# Grove_-_Capacitive_Moisture_Sensor_Corro.net
KiCad netlist of a schematic drawn in EAGLE
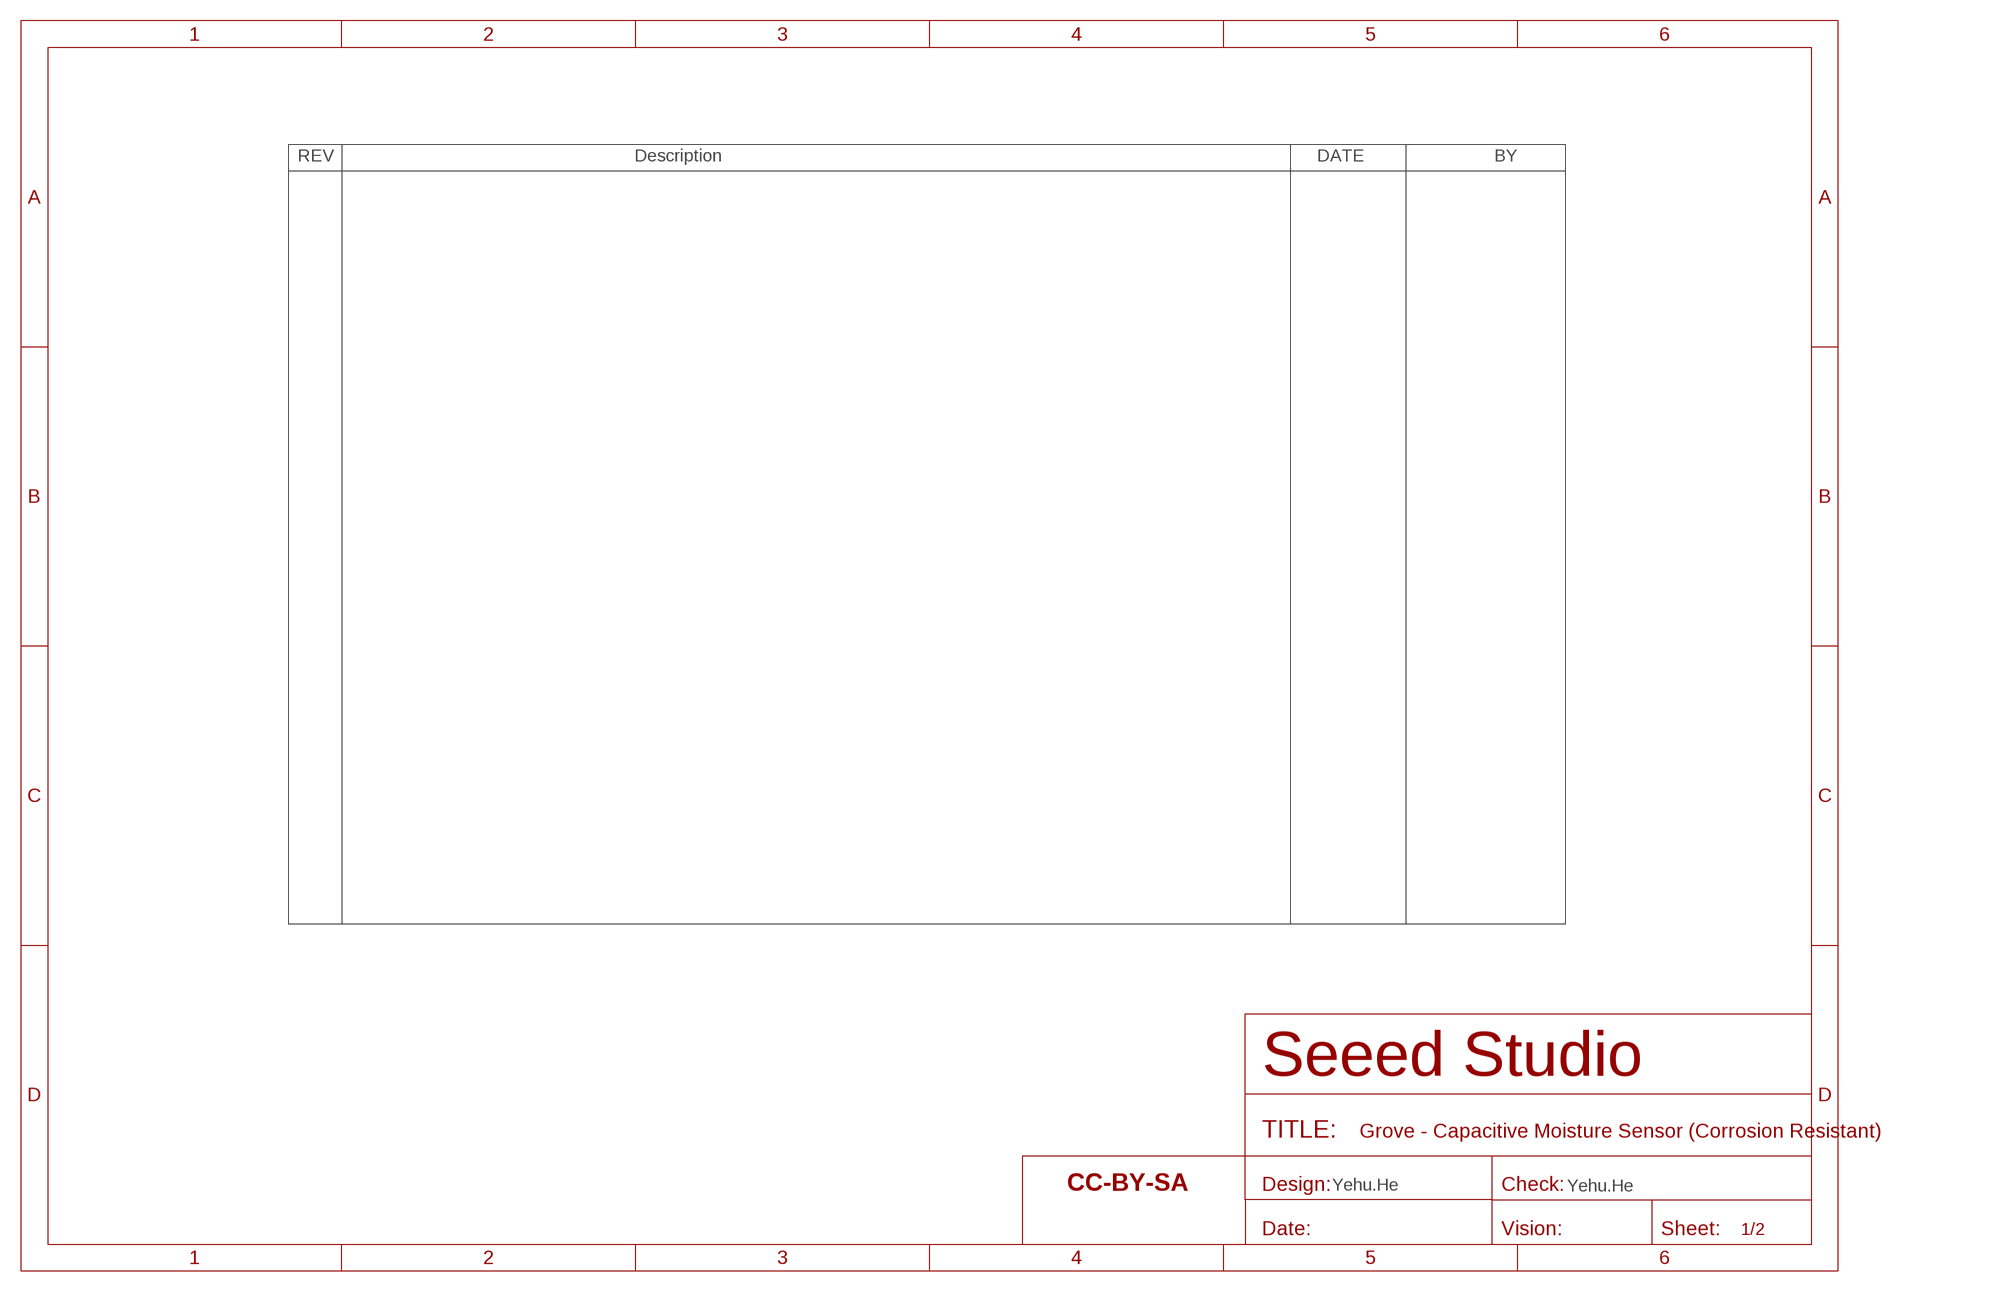
[diagram p0: schematic, sheet 1]
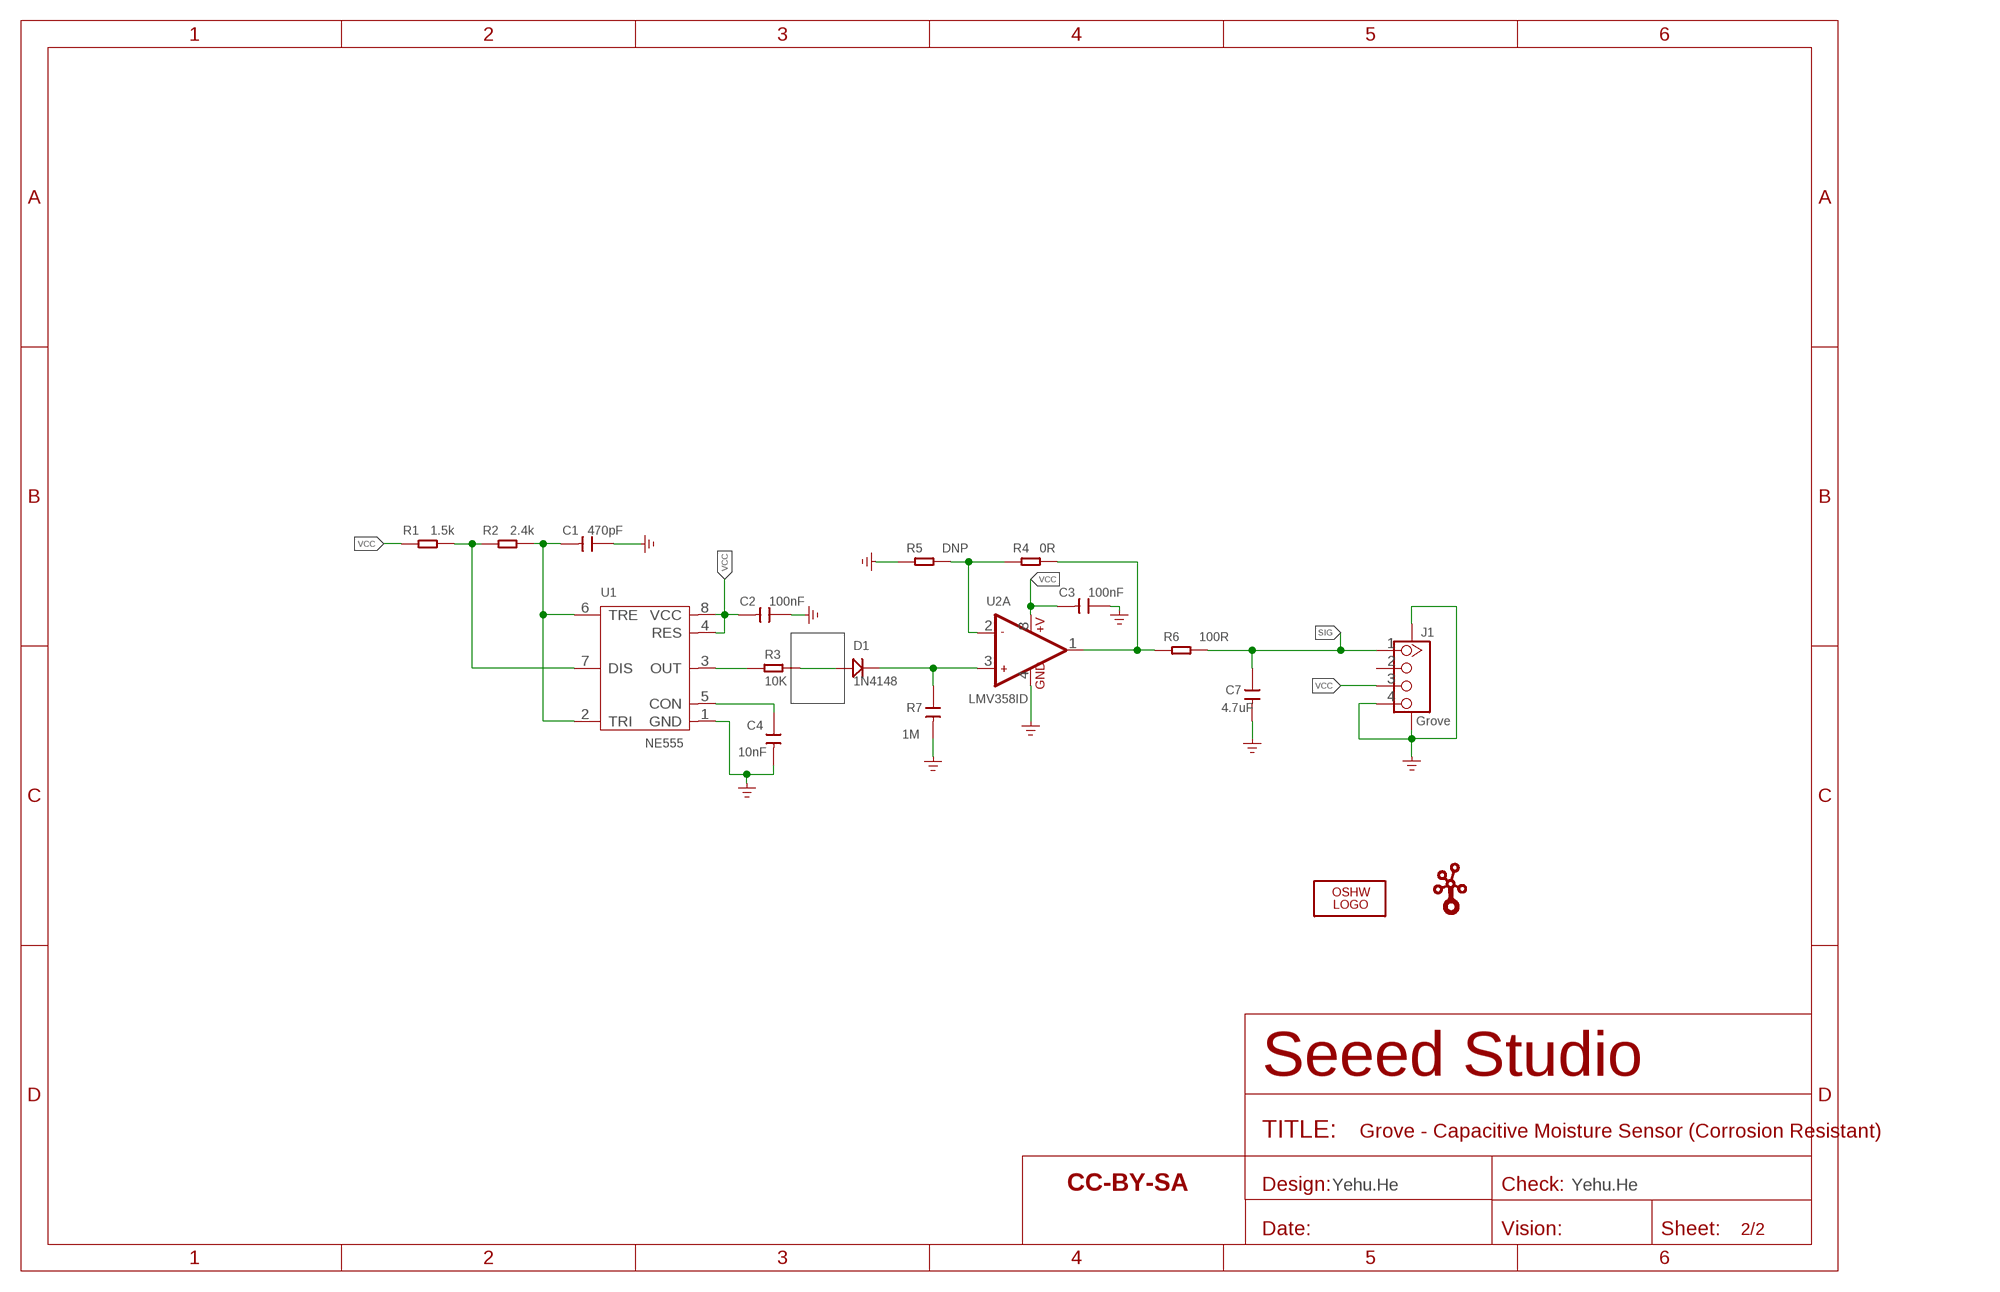
[diagram p1: schematic, sheet 2]

(export (version "E")
  (design (tool "Eeschema 10.0.6"))
  (components
    (comp (ref "C1")
      (value "470pF")
      (footprint "eagle-import:C0603")
      (libsource (lib "eagle-import") (part "CAP-0603"))
    )
    (comp (ref "C2")
      (value "100nF")
      (footprint "eagle-import:C0603")
      (libsource (lib "eagle-import") (part "CAP-0603"))
    )
    (comp (ref "C3")
      (value "100nF")
      (footprint "eagle-import:C0603")
      (libsource (lib "eagle-import") (part "CAP-0603"))
    )
    (comp (ref "C4")
      (value "10nF")
      (footprint "eagle-import:C0603")
      (libsource (lib "eagle-import") (part "CAP-0603"))
    )
    (comp (ref "C7")
      (value "4.7uF")
      (footprint "eagle-import:C0603")
      (libsource (lib "eagle-import") (part "CAP-0603"))
    )
    (comp (ref "D1")
      (value "1N4148")
      (footprint "eagle-import:LL-34")
      (libsource (lib "eagle-import") (part "DIODE'1N4148-SMD'"))
    )
    (comp (ref "FR2")
      (value "SEEEDSTUDIO-OPEN-SCH-FRAME")
      (footprint "eagle-import:SEEEDSTUDIO-PCB-FRAME")
      (libsource (lib "eagle-import") (part "SEEEDSTUDIO-OPEN-SCH-FRAME"))
    )
    (comp (ref "J1")
      (value "Grove")
      (footprint "eagle-import:HW4-SMD-2.0-90D")
      (libsource (lib "eagle-import") (part "GROVE-CONNECTOR-SMD'90D'"))
    )
    (comp (ref "LOGO1")
      (value "LOGO-OSHW-FILLX0200-NT")
      (footprint "eagle-import:OSHW_FILLX200_NOTEXT")
      (fields (field (name "PARTNO") "DNP"))
      (libsource (lib "eagle-import") (part "LOGO-OSHW-FILLX0200-NT"))
    )
    (comp (ref "R1")
      (value "1.5k")
      (footprint "eagle-import:R0603")
      (libsource (lib "eagle-import") (part "RES-0603"))
    )
    (comp (ref "R2")
      (value "2.4k")
      (footprint "eagle-import:R0603")
      (libsource (lib "eagle-import") (part "RES-0603"))
    )
    (comp (ref "R3")
      (value "10K")
      (footprint "eagle-import:R0603")
      (libsource (lib "eagle-import") (part "RES-0603"))
    )
    (comp (ref "R4")
      (value "0R")
      (footprint "eagle-import:R0603")
      (libsource (lib "eagle-import") (part "RES-0603"))
    )
    (comp (ref "R5")
      (value "DNP")
      (footprint "eagle-import:R0603")
      (libsource (lib "eagle-import") (part "RES-0603"))
    )
    (comp (ref "R6")
      (value "100R")
      (footprint "eagle-import:R0603")
      (libsource (lib "eagle-import") (part "RES-0603"))
    )
    (comp (ref "R7")
      (value "1M")
      (footprint "eagle-import:C0603")
      (libsource (lib "eagle-import") (part "CAP-0603"))
    )
    (comp (ref "U$7")
      (value "LOGO-GROVE")
      (footprint "eagle-import:GROVE-SILK-BIG")
      (fields (field (name "PARTNO") "DNP"))
      (libsource (lib "eagle-import") (part "LOGO-GROVE"))
    )
    (comp (ref "U1")
      (value "NE555")
      (footprint "eagle-import:SOIC8-1.27-5X4MM")
      (libsource (lib "eagle-import") (part "CLOCK/TIMING-NE555'DR'"))
    )
    (comp (ref "U2")
      (value "LMV358ID")
      (footprint "eagle-import:SOIC8-1.27-5X4MM")
      (libsource (lib "eagle-import") (part "AMPLIFIER-LMV358'D'"))
    )
    (comp (ref "FR1")
      (value "SEEEDSTUDIO-OPEN-SCH-FRAME")
      (footprint "eagle-import:SEEEDSTUDIO-PCB-FRAME")
      (libsource (lib "eagle-import") (part "SEEEDSTUDIO-OPEN-SCH-FRAME"))
    )
  )
  (nets
    (net (code "1") (name "GND") (class "Default")
      (node (ref "C1") (pin "1") (pinfunction "1_1") (pintype "passive"))
      (node (ref "C2") (pin "1") (pinfunction "1_1") (pintype "passive"))
      (node (ref "C3") (pin "1") (pinfunction "1_1") (pintype "passive"))
      (node (ref "C4") (pin "2") (pinfunction "2_2") (pintype "passive"))
      (node (ref "C7") (pin "2") (pinfunction "2_2") (pintype "passive"))
      (node (ref "J1") (pin "4") (pinfunction "4_4") (pintype "bidirectional"))
      (node (ref "J1") (pin "SS1") (pinfunction "SS1_SS1") (pintype "bidirectional"))
      (node (ref "J1") (pin "SS2") (pinfunction "SS2_SS2") (pintype "bidirectional"))
      (node (ref "R5") (pin "1") (pinfunction "1_1") (pintype "passive"))
      (node (ref "R7") (pin "2") (pinfunction "2_2") (pintype "passive"))
      (node (ref "U1") (pin "1") (pinfunction "GND_1") (pintype "bidirectional"))
      (node (ref "U2") (pin "4") (pinfunction "GND_4") (pintype "power_in"))
    )
    (net (code "2") (name "Net-(D1-+)") (class "Default")
      (node (ref "D1") (pin "A") (pinfunction "+_A") (pintype "passive"))
      (node (ref "R3") (pin "2") (pinfunction "2_2") (pintype "passive"))
    )
    (net (code "3") (name "Net-(D1--)") (class "Default")
      (node (ref "D1") (pin "C") (pinfunction "-_C") (pintype "passive"))
      (node (ref "R7") (pin "1") (pinfunction "1_1") (pintype "passive"))
      (node (ref "U2") (pin "3") (pinfunction "+IN1_3") (pintype "input"))
    )
    (net (code "4") (name "Net-(U1-CON)") (class "Default")
      (node (ref "C4") (pin "1") (pinfunction "1_1") (pintype "passive"))
      (node (ref "U1") (pin "5") (pinfunction "CON_5") (pintype "bidirectional"))
    )
    (net (code "5") (name "Net-(U1-DIS)") (class "Default")
      (node (ref "R1") (pin "1") (pinfunction "1_1") (pintype "passive"))
      (node (ref "R2") (pin "2") (pinfunction "2_2") (pintype "passive"))
      (node (ref "U1") (pin "7") (pinfunction "DIS_7") (pintype "bidirectional"))
    )
    (net (code "6") (name "Net-(U1-OUT)") (class "Default")
      (node (ref "R3") (pin "1") (pinfunction "1_1") (pintype "passive"))
      (node (ref "U1") (pin "3") (pinfunction "OUT_3") (pintype "bidirectional"))
    )
    (net (code "7") (name "Net-(U1-TRE)") (class "Default")
      (node (ref "C1") (pin "2") (pinfunction "2_2") (pintype "passive"))
      (node (ref "R2") (pin "1") (pinfunction "1_1") (pintype "passive"))
      (node (ref "U1") (pin "2") (pinfunction "TRI_2") (pintype "bidirectional"))
      (node (ref "U1") (pin "6") (pinfunction "TRE_6") (pintype "bidirectional"))
    )
    (net (code "8") (name "Net-(U2A--IN1)") (class "Default")
      (node (ref "R4") (pin "1") (pinfunction "1_1") (pintype "passive"))
      (node (ref "R5") (pin "2") (pinfunction "2_2") (pintype "passive"))
      (node (ref "U2") (pin "2") (pinfunction "-IN1_2") (pintype "input"))
    )
    (net (code "9") (name "Net-(U2A-OUT1)") (class "Default")
      (node (ref "R4") (pin "2") (pinfunction "2_2") (pintype "passive"))
      (node (ref "R6") (pin "1") (pinfunction "1_1") (pintype "passive"))
      (node (ref "U2") (pin "1") (pinfunction "OUT1_1") (pintype "output"))
    )
    (net (code "10") (name "SIG") (class "Default")
      (node (ref "C7") (pin "1") (pinfunction "1_1") (pintype "passive"))
      (node (ref "J1") (pin "1") (pinfunction "1_1") (pintype "bidirectional"))
      (node (ref "R6") (pin "2") (pinfunction "2_2") (pintype "passive"))
    )
    (net (code "11") (name "VCC") (class "Default")
      (node (ref "C2") (pin "2") (pinfunction "2_2") (pintype "passive"))
      (node (ref "C3") (pin "2") (pinfunction "2_2") (pintype "passive"))
      (node (ref "J1") (pin "3") (pinfunction "3_3") (pintype "bidirectional"))
      (node (ref "R1") (pin "2") (pinfunction "2_2") (pintype "passive"))
      (node (ref "U1") (pin "4") (pinfunction "RES_4") (pintype "bidirectional"))
      (node (ref "U1") (pin "8") (pinfunction "VCC_8") (pintype "bidirectional"))
      (node (ref "U2") (pin "8") (pinfunction "+V_8") (pintype "power_in"))
    )
    (net (code "12") (name "unconnected-(J1-Pad2)") (class "Default")
      (node (ref "J1") (pin "2") (pinfunction "2_2") (pintype "bidirectional"))
    )
  )
)
